# Arduino_DUE.net
KiCad netlist of a schematic drawn in Altium Designer
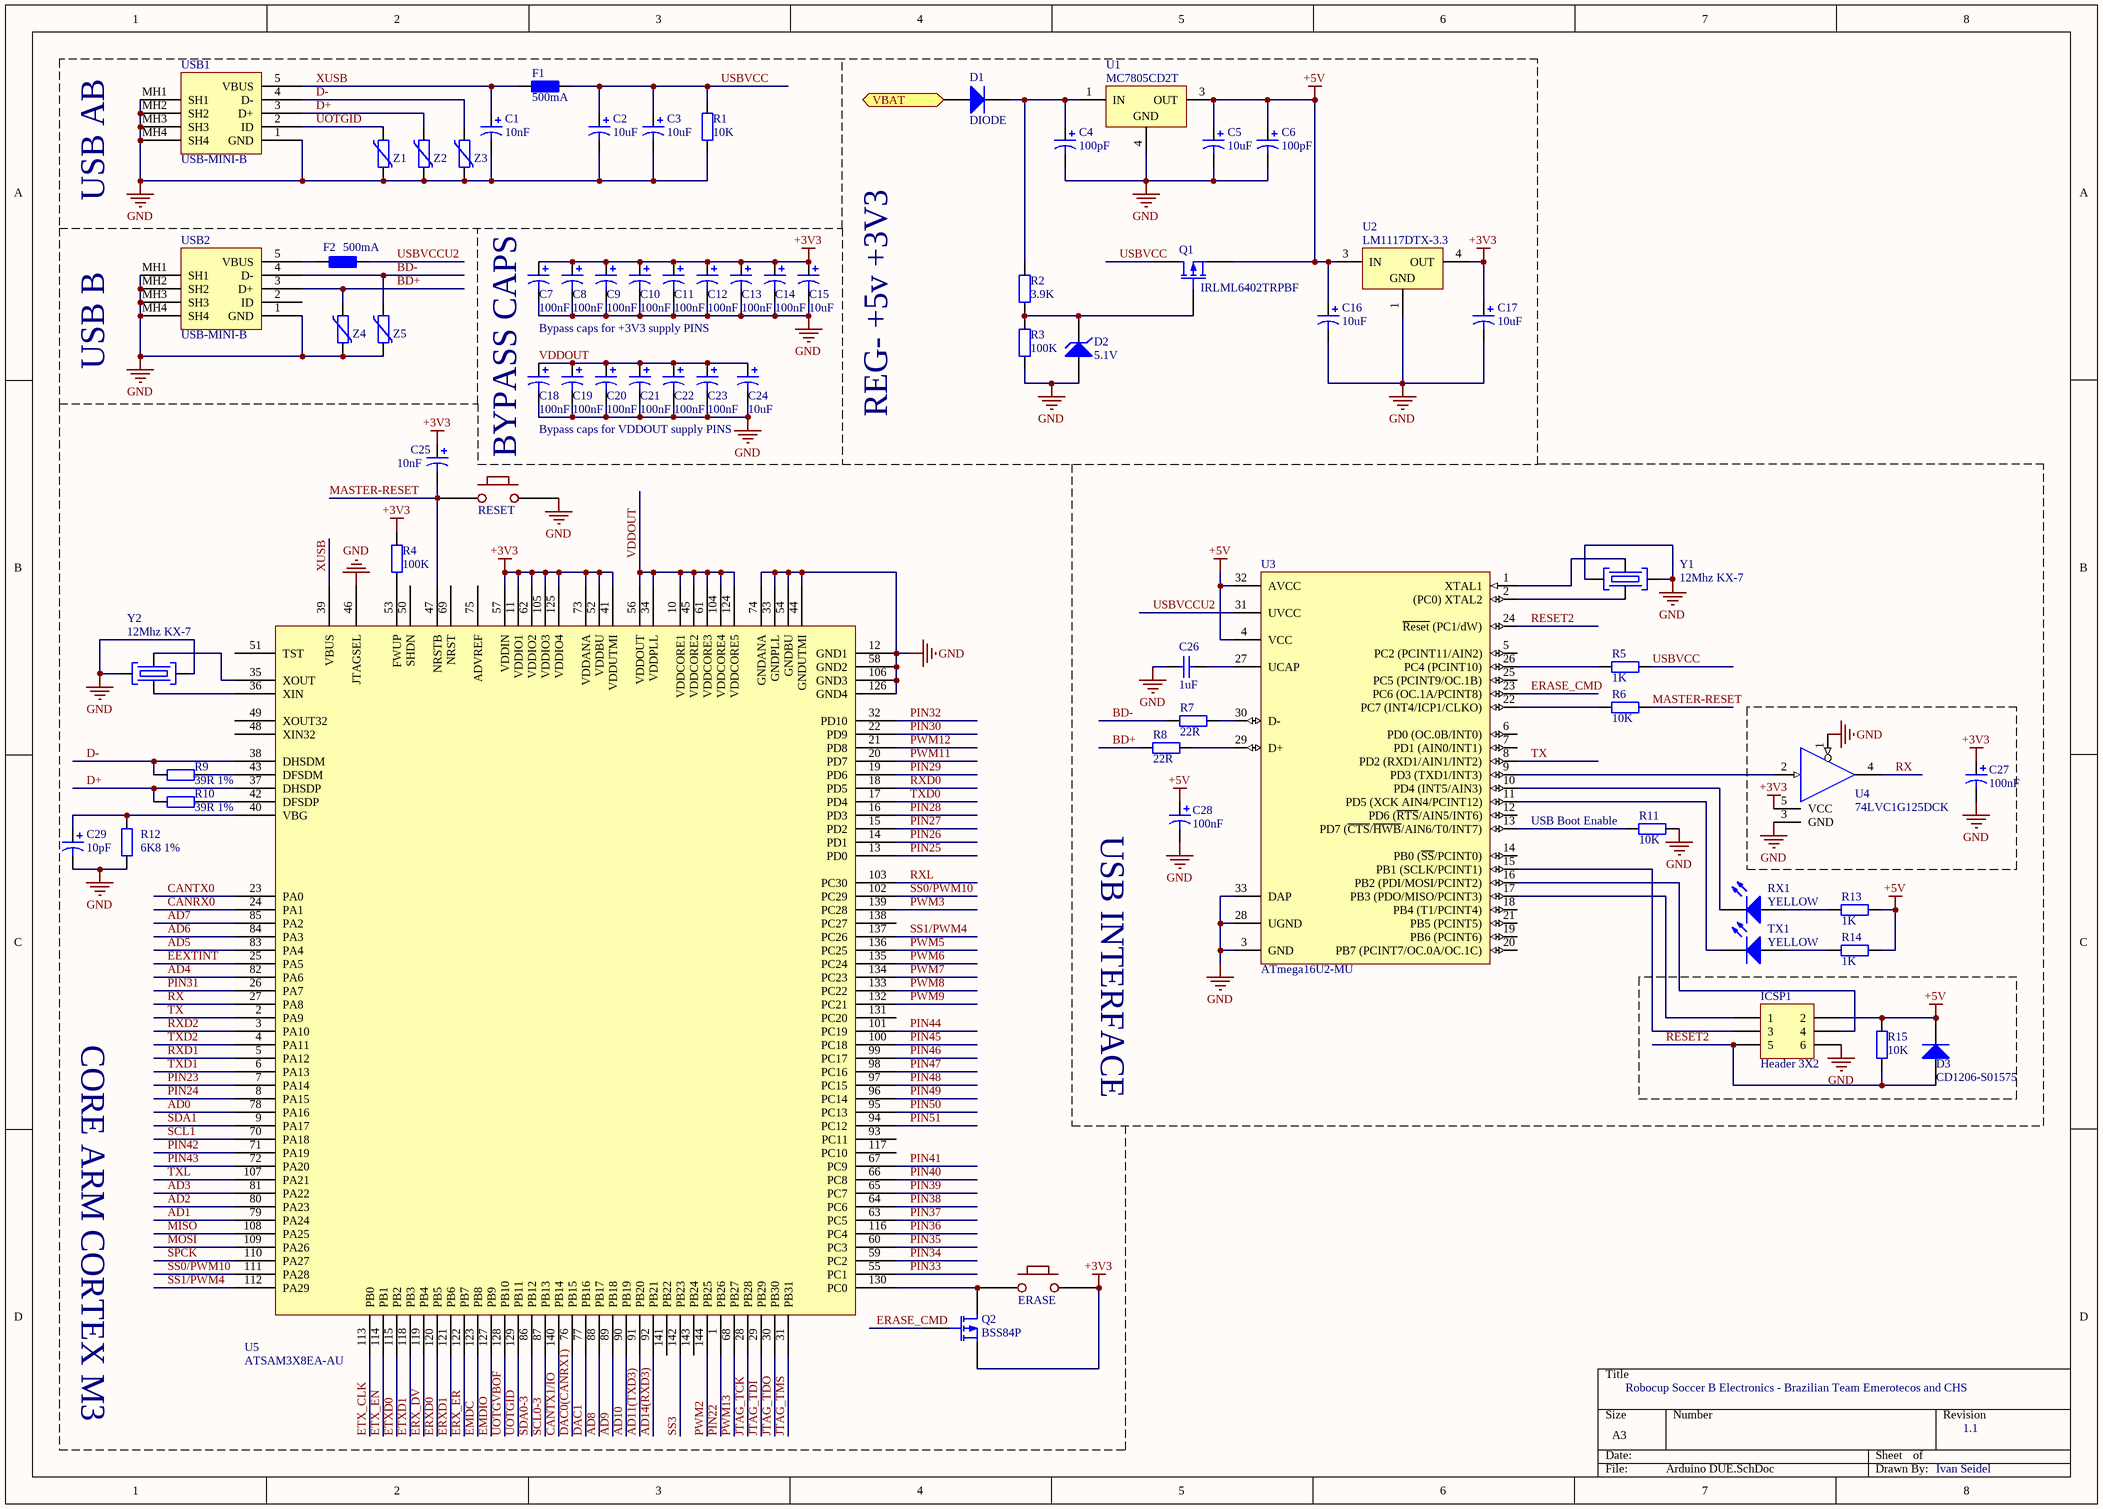
[diagram p0: Arduino DUE.SchDoc]

(export (version "E")
  (design (tool "Eeschema 10.0.6"))
  (components
    (comp (ref "C1")
      (value "10nF")
      (footprint "C0805")
      (description "Polarized Capacitor (Surface Mount)")
      (fields (field (name "PUBLISHER") "Altium Limited"))
      (libsource (lib "Miscellaneous Devices") (part "Cap Pol3"))
    )
    (comp (ref "C2")
      (value "10uF")
      (footprint "3528")
      (description "Polarized Capacitor (Surface Mount)")
      (fields (field (name "PUBLISHER") "Altium Limited"))
      (libsource (lib "Miscellaneous Devices") (part "Cap Pol3"))
    )
    (comp (ref "C3")
      (value "10uF")
      (footprint "3528")
      (description "Polarized Capacitor (Surface Mount)")
      (fields (field (name "PUBLISHER") "Altium Limited"))
      (libsource (lib "Miscellaneous Devices") (part "Cap Pol3"))
    )
    (comp (ref "C4")
      (value "100pF")
      (footprint "C0805")
      (description "Polarized Capacitor (Surface Mount)")
      (fields (field (name "PUBLISHER") "Altium Limited"))
      (libsource (lib "Miscellaneous Devices") (part "Cap Pol3"))
    )
    (comp (ref "C5")
      (value "10uF")
      (footprint "3528")
      (description "Polarized Capacitor (Surface Mount)")
      (fields (field (name "PUBLISHER") "Altium Limited"))
      (libsource (lib "Miscellaneous Devices") (part "Cap Pol3"))
    )
    (comp (ref "C6")
      (value "100pF")
      (footprint "C0805")
      (description "Polarized Capacitor (Surface Mount)")
      (fields (field (name "PUBLISHER") "Altium Limited"))
      (libsource (lib "Miscellaneous Devices") (part "Cap Pol3"))
    )
    (comp (ref "C7")
      (value "100nF")
      (footprint "C0805")
      (description "Polarized Capacitor (Surface Mount)")
      (fields (field (name "PUBLISHER") "Altium Limited"))
      (libsource (lib "Miscellaneous Devices") (part "Cap Pol3"))
    )
    (comp (ref "C8")
      (value "100nF")
      (footprint "C0805")
      (description "Polarized Capacitor (Surface Mount)")
      (fields (field (name "PUBLISHER") "Altium Limited"))
      (libsource (lib "Miscellaneous Devices") (part "Cap Pol3"))
    )
    (comp (ref "C9")
      (value "100nF")
      (footprint "C0805")
      (description "Polarized Capacitor (Surface Mount)")
      (fields (field (name "PUBLISHER") "Altium Limited"))
      (libsource (lib "Miscellaneous Devices") (part "Cap Pol3"))
    )
    (comp (ref "C10")
      (value "100nF")
      (footprint "C0805")
      (description "Polarized Capacitor (Surface Mount)")
      (fields (field (name "PUBLISHER") "Altium Limited"))
      (libsource (lib "Miscellaneous Devices") (part "Cap Pol3"))
    )
    (comp (ref "C11")
      (value "100nF")
      (footprint "C0805")
      (description "Polarized Capacitor (Surface Mount)")
      (fields (field (name "PUBLISHER") "Altium Limited"))
      (libsource (lib "Miscellaneous Devices") (part "Cap Pol3"))
    )
    (comp (ref "C12")
      (value "100nF")
      (footprint "C0805")
      (description "Polarized Capacitor (Surface Mount)")
      (fields (field (name "PUBLISHER") "Altium Limited"))
      (libsource (lib "Miscellaneous Devices") (part "Cap Pol3"))
    )
    (comp (ref "C13")
      (value "100nF")
      (footprint "C0805")
      (description "Polarized Capacitor (Surface Mount)")
      (fields (field (name "PUBLISHER") "Altium Limited"))
      (libsource (lib "Miscellaneous Devices") (part "Cap Pol3"))
    )
    (comp (ref "C14")
      (value "100nF")
      (footprint "C0805")
      (description "Polarized Capacitor (Surface Mount)")
      (fields (field (name "PUBLISHER") "Altium Limited"))
      (libsource (lib "Miscellaneous Devices") (part "Cap Pol3"))
    )
    (comp (ref "C15")
      (value "10uF")
      (footprint "3528")
      (description "Polarized Capacitor (Surface Mount)")
      (fields (field (name "PUBLISHER") "Altium Limited"))
      (libsource (lib "Miscellaneous Devices") (part "Cap Pol3"))
    )
    (comp (ref "C16")
      (value "10uF")
      (footprint "3528")
      (description "Polarized Capacitor (Surface Mount)")
      (fields (field (name "PUBLISHER") "Altium Limited"))
      (libsource (lib "Miscellaneous Devices") (part "Cap Pol3"))
    )
    (comp (ref "C17")
      (value "10uF")
      (footprint "3528")
      (description "Polarized Capacitor (Surface Mount)")
      (fields (field (name "PUBLISHER") "Altium Limited"))
      (libsource (lib "Miscellaneous Devices") (part "Cap Pol3"))
    )
    (comp (ref "C18")
      (value "100nF")
      (footprint "C0805")
      (description "Polarized Capacitor (Surface Mount)")
      (fields (field (name "PUBLISHER") "Altium Limited"))
      (libsource (lib "Miscellaneous Devices") (part "Cap Pol3"))
    )
    (comp (ref "C19")
      (value "100nF")
      (footprint "C0805")
      (description "Polarized Capacitor (Surface Mount)")
      (fields (field (name "PUBLISHER") "Altium Limited"))
      (libsource (lib "Miscellaneous Devices") (part "Cap Pol3"))
    )
    (comp (ref "C20")
      (value "100nF")
      (footprint "C0805")
      (description "Polarized Capacitor (Surface Mount)")
      (fields (field (name "PUBLISHER") "Altium Limited"))
      (libsource (lib "Miscellaneous Devices") (part "Cap Pol3"))
    )
    (comp (ref "C21")
      (value "100nF")
      (footprint "C0805")
      (description "Polarized Capacitor (Surface Mount)")
      (fields (field (name "PUBLISHER") "Altium Limited"))
      (libsource (lib "Miscellaneous Devices") (part "Cap Pol3"))
    )
    (comp (ref "C22")
      (value "100nF")
      (footprint "C0805")
      (description "Polarized Capacitor (Surface Mount)")
      (fields (field (name "PUBLISHER") "Altium Limited"))
      (libsource (lib "Miscellaneous Devices") (part "Cap Pol3"))
    )
    (comp (ref "C23")
      (value "100nF")
      (footprint "C0805")
      (description "Polarized Capacitor (Surface Mount)")
      (fields (field (name "PUBLISHER") "Altium Limited"))
      (libsource (lib "Miscellaneous Devices") (part "Cap Pol3"))
    )
    (comp (ref "C24")
      (value "10uF")
      (footprint "3528")
      (description "Polarized Capacitor (Surface Mount)")
      (fields (field (name "PUBLISHER") "Altium Limited"))
      (libsource (lib "Miscellaneous Devices") (part "Cap Pol3"))
    )
    (comp (ref "C25")
      (value "10nF")
      (footprint "C0805")
      (description "Polarized Capacitor (Surface Mount)")
      (fields (field (name "PUBLISHER") "Altium Limited"))
      (libsource (lib "Miscellaneous Devices") (part "Cap Pol3"))
    )
    (comp (ref "C26")
      (value "1uF")
      (footprint "0402")
      (description "Capacitor (Semiconductor SIM Model)")
      (fields (field (name "PUBLISHER") "Altium Limited"))
      (libsource (lib "Miscellaneous Devices") (part "Cap Semi"))
    )
    (comp (ref "C27")
      (value "100nF")
      (footprint "C0805")
      (description "Polarized Capacitor (Surface Mount)")
      (fields (field (name "PUBLISHER") "Altium Limited"))
      (libsource (lib "Miscellaneous Devices") (part "Cap Pol3"))
    )
    (comp (ref "C28")
      (value "100nF")
      (footprint "C0805")
      (description "Polarized Capacitor (Surface Mount)")
      (fields (field (name "PUBLISHER") "Altium Limited"))
      (libsource (lib "Miscellaneous Devices") (part "Cap Pol3"))
    )
    (comp (ref "C29")
      (value "10pF")
      (footprint "C0805")
      (description "Polarized Capacitor (Surface Mount)")
      (fields (field (name "PUBLISHER") "Altium Limited"))
      (libsource (lib "Miscellaneous Devices") (part "Cap Pol3"))
    )
    (comp (ref "D1") (value "DIODE") (footprint "DIODESMA") (libsource (lib "CustomLibrary") (part "DIODE")))
    (comp (ref "D2")
      (value "5.1V")
      (footprint "DIODE-SOD-123")
      (description "ZENER DIODE")
      (libsource (lib "CustomLibrary") (part "ZENER"))
    )
    (comp (ref "D3")
      (value "CD1206-S01575")
      (footprint "DIODE1206")
      (libsource (lib "CustomLibrary") (part "DIODE"))
    )
    (comp (ref "ERASE")
      (value "PUSH BUTTON")
      (footprint "PUSH-BUTTON 5,2X1,6MM")
      (libsource (lib "CustomLibrary") (part "PUSH BUTTON"))
    )
    (comp (ref "F1")
      (value "500mA")
      (footprint "MF-MSMF")
      (description "MF-MSMF Series - PTC Resettable Fuses")
      (libsource (lib "CustomLibrary") (part "MF-MSMF"))
    )
    (comp (ref "F2")
      (value "500mA")
      (footprint "MF-MSMF")
      (description "MF-MSMF Series - PTC Resettable Fuses")
      (libsource (lib "CustomLibrary") (part "MF-MSMF"))
    )
    (comp (ref "ICSP1")
      (value "Header 3X2")
      (footprint "HDR2X3")
      (description "Header, 3-Pin, Dual row")
      (fields (field (name "PUBLISHER") "Altium Limited"))
      (libsource (lib "Miscellaneous Connectors") (part "Header 3X2"))
    )
    (comp (ref "Q1")
      (value "IRLML6402TRPBF")
      (footprint "SOT-23")
      (description "P-Channel MOSFET")
      (fields (field (name "PUBLISHER") "Altium Limited"))
      (libsource (lib "CustomLibrary") (part "MOSFET-P"))
    )
    (comp (ref "Q2")
      (value "BSS84P")
      (footprint "SOT-23")
      (description "P-Channel MOSFET")
      (fields (field (name "PUBLISHER") "Altium Limited"))
      (libsource (lib "CustomLibrary") (part "MOSFET-P"))
    )
    (comp (ref "R1") (value "10K") (footprint "RES1206") (libsource (lib "") (part "RES_1")))
    (comp (ref "R2") (value "3.9K") (footprint "RES1206") (libsource (lib "") (part "RES_1")))
    (comp (ref "R3") (value "100K") (footprint "RES1206") (libsource (lib "") (part "RES_1")))
    (comp (ref "R4") (value "100K") (footprint "RES1206") (libsource (lib "") (part "RES_1")))
    (comp (ref "R5") (value "1K") (footprint "RES1206") (libsource (lib "CustomLibrary") (part "RES")))
    (comp (ref "R6") (value "10K") (footprint "RES1206") (libsource (lib "CustomLibrary") (part "RES")))
    (comp (ref "R7") (value "22R") (footprint "RES1206") (libsource (lib "CustomLibrary") (part "RES")))
    (comp (ref "R8") (value "22R") (footprint "RES1206") (libsource (lib "CustomLibrary") (part "RES")))
    (comp (ref "R9") (value "39R 1%") (footprint "RES1206") (libsource (lib "") (part "RES_2")))
    (comp (ref "R10") (value "39R 1%") (footprint "RES1206") (libsource (lib "") (part "RES_2")))
    (comp (ref "R11") (value "10K") (footprint "RES1206") (libsource (lib "CustomLibrary") (part "RES")))
    (comp (ref "R12") (value "6K8 1%") (footprint "RES1206") (libsource (lib "") (part "RES_1")))
    (comp (ref "R13") (value "1K") (footprint "RES1206") (libsource (lib "CustomLibrary") (part "RES")))
    (comp (ref "R14") (value "1K") (footprint "RES1206") (libsource (lib "CustomLibrary") (part "RES")))
    (comp (ref "R15") (value "10K") (footprint "RES1206") (libsource (lib "") (part "RES_1")))
    (comp (ref "RESET")
      (value "RESET")
      (footprint "PUSH-BUTTON 5,2X1,6MM")
      (libsource (lib "CustomLibrary") (part "PUSH BUTTON"))
    )
    (comp (ref "RX1") (value "YELLOW") (footprint "LED0805") (libsource (lib "CustomLibrary") (part "LED")))
    (comp (ref "TX1") (value "YELLOW") (footprint "LED0805") (libsource (lib "CustomLibrary") (part "LED")))
    (comp (ref "U1")
      (value "MC7805CD2T")
      (footprint "936-03")
      (description "Three-Terminal Positive Voltage Regulator")
      (fields (field (name "PUBLISHER") "Altium Limited"))
      (libsource (lib "ON Semi Power Mgt Voltage Regulator") (part "MC7805CD2T"))
    )
    (comp (ref "U2")
      (value "LM1117DTX-3.3")
      (footprint "TD03B_N")
      (description "800mA Low-Dropout Linear Regulator, 3-pin TO-252")
      (fields
        (field (name "MANUFACTURER") "National Semiconductor")
        (field (name "PUBLISHER") "Altium Limited")
      )
      (libsource (lib "NSC LDO") (part "LM1117DTX-3.3"))
    )
    (comp (ref "U3")
      (value "ATmega16U2-MU")
      (footprint "32PG_N")
      (fields (field (name "PUBLISHER") "Altium Limited"))
      (libsource (lib "Atmel Microcontroller 8-Bit megaAVR") (part "ATmega16U2-MU"))
    )
    (comp (ref "U4")
      (value "74LVC1G125DCK")
      (footprint "SC70-5")
      (libsource (lib "CustomLibrary") (part "74LVC1G125DCK"))
    )
    (comp (ref "U5")
      (value "ATSAM3X8EA-AU")
      (footprint "LQFP144_M")
      (description "ATSAM3X8EA-AU ARM CORTEX M3 Microcontroller")
      (libsource (lib "CustomLibrary") (part "ATSAM3X8E"))
    )
    (comp (ref "USB1")
      (value "USB-MINI-B")
      (footprint "USB-MINI-B")
      (description "USB Mini type B Horizontal SMD")
      (libsource (lib "CustomLibrary") (part "USB-MINI-B"))
    )
    (comp (ref "USB2")
      (value "USB-MINI-B")
      (footprint "USB-MINI-B")
      (description "USB Mini type B Horizontal SMD")
      (libsource (lib "CustomLibrary") (part "USB-MINI-B"))
    )
    (comp (ref "Y1")
      (value "12Mhz KX-7")
      (footprint "OSC-4-PIN")
      (description "KX-7 12MHz Oscilator 20pF")
      (libsource (lib "CustomLibrary") (part "OSC-4-PIN"))
    )
    (comp (ref "Y2")
      (value "12Mhz KX-7")
      (footprint "OSC-4-PIN")
      (description "KX-7 12MHz Oscilator 20pF")
      (libsource (lib "CustomLibrary") (part "OSC-4-PIN"))
    )
    (comp (ref "Z1")
      (value "ESD")
      (footprint "ESD0603")
      (description "ESD Protection Diode")
      (libsource (lib "CustomLibrary") (part "ESD"))
    )
    (comp (ref "Z2")
      (value "ESD")
      (footprint "ESD0603")
      (description "ESD Protection Diode")
      (libsource (lib "CustomLibrary") (part "ESD"))
    )
    (comp (ref "Z3")
      (value "ESD")
      (footprint "ESD0603")
      (description "ESD Protection Diode")
      (libsource (lib "CustomLibrary") (part "ESD"))
    )
    (comp (ref "Z4")
      (value "ESD")
      (footprint "ESD0603")
      (description "ESD Protection Diode")
      (libsource (lib "CustomLibrary") (part "ESD"))
    )
    (comp (ref "Z5")
      (value "ESD")
      (footprint "ESD0603")
      (description "ESD Protection Diode")
      (libsource (lib "CustomLibrary") (part "ESD"))
    )
  )
  (nets
    (net (code "1") (name "+3V3") (class "Default")
      (node (ref "C10") (pin "1") (pinfunction "1_1") (pintype "passive"))
      (node (ref "C11") (pin "1") (pinfunction "1_1") (pintype "passive"))
      (node (ref "C12") (pin "1") (pinfunction "1_1") (pintype "passive"))
      (node (ref "C13") (pin "1") (pinfunction "1_1") (pintype "passive"))
      (node (ref "C14") (pin "1") (pinfunction "1_1") (pintype "passive"))
      (node (ref "C15") (pin "1") (pinfunction "1_1") (pintype "passive"))
      (node (ref "C17") (pin "1") (pinfunction "1_1") (pintype "passive"))
      (node (ref "C25") (pin "1") (pinfunction "1_1") (pintype "passive"))
      (node (ref "C27") (pin "1") (pinfunction "1_1") (pintype "passive"))
      (node (ref "C7") (pin "1") (pinfunction "1_1") (pintype "passive"))
      (node (ref "C8") (pin "1") (pinfunction "1_1") (pintype "passive"))
      (node (ref "C9") (pin "1") (pinfunction "1_1") (pintype "passive"))
      (node (ref "ERASE") (pin "2") (pinfunction "2_2") (pintype "passive"))
      (node (ref "Q2") (pin "2") (pinfunction "S_2") (pintype "passive"))
      (node (ref "R4") (pin "2") (pinfunction "2_2") (pintype "passive"))
      (node (ref "U2") (pin "4") (pinfunction "OUT_4") (pintype "power_in"))
      (node (ref "U4") (pin "5") (pinfunction "VCC_5") (pintype "power_in"))
      (node (ref "U5") (pin "105") (pinfunction "VDDIO3_105") (pintype "power_in"))
      (node (ref "U5") (pin "11") (pinfunction "VDDIO1_11") (pintype "power_in"))
      (node (ref "U5") (pin "125") (pinfunction "VDDIO4_125") (pintype "power_in"))
      (node (ref "U5") (pin "41") (pinfunction "VDDUTMI_41") (pintype "power_in"))
      (node (ref "U5") (pin "52") (pinfunction "VDDBU_52") (pintype "power_in"))
      (node (ref "U5") (pin "57") (pinfunction "VDDIN_57") (pintype "power_in"))
      (node (ref "U5") (pin "62") (pinfunction "VDDIO2_62") (pintype "power_in"))
      (node (ref "U5") (pin "73") (pinfunction "VDDANA_73") (pintype "power_in"))
    )
    (net (code "2") (name "+5V") (class "Default")
      (node (ref "C16") (pin "1") (pinfunction "1_1") (pintype "passive"))
      (node (ref "C28") (pin "1") (pinfunction "1_1") (pintype "passive"))
      (node (ref "C5") (pin "1") (pinfunction "1_1") (pintype "passive"))
      (node (ref "C6") (pin "1") (pinfunction "1_1") (pintype "passive"))
      (node (ref "D3") (pin "1") (pinfunction "K_1") (pintype "passive"))
      (node (ref "ICSP1") (pin "2") (pinfunction "2_2") (pintype "passive"))
      (node (ref "Q1") (pin "2") (pinfunction "S_2") (pintype "passive"))
      (node (ref "R13") (pin "2") (pinfunction "2_2") (pintype "passive"))
      (node (ref "R14") (pin "2") (pinfunction "2_2") (pintype "passive"))
      (node (ref "R15") (pin "2") (pinfunction "2_2") (pintype "passive"))
      (node (ref "U1") (pin "3") (pinfunction "OUT_3") (pintype "power_in"))
      (node (ref "U2") (pin "3") (pinfunction "IN_3") (pintype "power_in"))
      (node (ref "U3") (pin "32") (pinfunction "AVCC_32") (pintype "power_in"))
      (node (ref "U3") (pin "4") (pinfunction "VCC_4") (pintype "power_in"))
    )
    (net (code "3") (name "/AD0") (class "Default")
      (node (ref "U5") (pin "78") (pinfunction "PA16_78") (pintype "passive"))
    )
    (net (code "4") (name "/AD1") (class "Default")
      (node (ref "U5") (pin "79") (pinfunction "PA24_79") (pintype "passive"))
    )
    (net (code "5") (name "/AD2") (class "Default")
      (node (ref "U5") (pin "80") (pinfunction "PA23_80") (pintype "passive"))
    )
    (net (code "6") (name "/AD3") (class "Default")
      (node (ref "U5") (pin "81") (pinfunction "PA22_81") (pintype "passive"))
    )
    (net (code "7") (name "/AD4") (class "Default")
      (node (ref "U5") (pin "82") (pinfunction "PA6_82") (pintype "passive"))
    )
    (net (code "8") (name "/AD5") (class "Default")
      (node (ref "U5") (pin "83") (pinfunction "PA4_83") (pintype "passive"))
    )
    (net (code "9") (name "/AD6") (class "Default")
      (node (ref "U5") (pin "84") (pinfunction "PA3_84") (pintype "passive"))
    )
    (net (code "10") (name "/AD7") (class "Default")
      (node (ref "U5") (pin "85") (pinfunction "PA2_85") (pintype "passive"))
    )
    (net (code "11") (name "/AD8") (class "Default")
      (node (ref "U5") (pin "88") (pinfunction "PB17_88") (pintype "passive"))
    )
    (net (code "12") (name "/AD9") (class "Default")
      (node (ref "U5") (pin "89") (pinfunction "PB18_89") (pintype "passive"))
    )
    (net (code "13") (name "/AD10") (class "Default")
      (node (ref "U5") (pin "90") (pinfunction "PB19_90") (pintype "passive"))
    )
    (net (code "14") (name "/AD11(TXD3)") (class "Default")
      (node (ref "U5") (pin "91") (pinfunction "PB20_91") (pintype "passive"))
    )
    (net (code "15") (name "/AD14(RXD3)") (class "Default")
      (node (ref "U5") (pin "92") (pinfunction "PB21_92") (pintype "passive"))
    )
    (net (code "16") (name "/BD+") (class "Default")
      (node (ref "R8") (pin "1") (pinfunction "1_1") (pintype "passive"))
      (node (ref "USB2") (pin "3") (pinfunction "D+_3") (pintype "passive"))
      (node (ref "Z4") (pin "2") (pinfunction "2_2") (pintype "passive"))
    )
    (net (code "17") (name "/BD-") (class "Default")
      (node (ref "R7") (pin "1") (pinfunction "1_1") (pintype "passive"))
      (node (ref "USB2") (pin "4") (pinfunction "D-_4") (pintype "passive"))
      (node (ref "Z5") (pin "2") (pinfunction "2_2") (pintype "passive"))
    )
    (net (code "18") (name "/CANRX0") (class "Default")
      (node (ref "U5") (pin "24") (pinfunction "PA1_24") (pintype "passive"))
    )
    (net (code "19") (name "/CANTX0") (class "Default")
      (node (ref "U5") (pin "23") (pinfunction "PA0_23") (pintype "passive"))
    )
    (net (code "20") (name "/CANTX1{slash}IO") (class "Default")
      (node (ref "U5") (pin "140") (pinfunction "PB14_140") (pintype "passive"))
    )
    (net (code "21") (name "/D+") (class "Default")
      (node (ref "R10") (pin "2") (pinfunction "2_2") (pintype "passive"))
      (node (ref "U5") (pin "37") (pinfunction "DHSDP_37") (pintype "passive"))
      (node (ref "USB1") (pin "3") (pinfunction "D+_3") (pintype "passive"))
      (node (ref "Z2") (pin "2") (pinfunction "2_2") (pintype "passive"))
    )
    (net (code "22") (name "/D-") (class "Default")
      (node (ref "R9") (pin "2") (pinfunction "2_2") (pintype "passive"))
      (node (ref "U5") (pin "38") (pinfunction "DHSDM_38") (pintype "passive"))
      (node (ref "USB1") (pin "4") (pinfunction "D-_4") (pintype "passive"))
      (node (ref "Z3") (pin "2") (pinfunction "2_2") (pintype "passive"))
    )
    (net (code "23") (name "/DAC0(CANRX1)") (class "Default")
      (node (ref "U5") (pin "76") (pinfunction "PB15_76") (pintype "passive"))
    )
    (net (code "24") (name "/DAC1") (class "Default")
      (node (ref "U5") (pin "77") (pinfunction "PB16_77") (pintype "passive"))
    )
    (net (code "25") (name "/EEXTINT") (class "Default")
      (node (ref "U5") (pin "25") (pinfunction "PA5_25") (pintype "passive"))
    )
    (net (code "26") (name "/EMDC") (class "Default")
      (node (ref "U5") (pin "123") (pinfunction "PB8_123") (pintype "passive"))
    )
    (net (code "27") (name "/EMDIO") (class "Default")
      (node (ref "U5") (pin "127") (pinfunction "PB9_127") (pintype "passive"))
    )
    (net (code "28") (name "/ERASE_CMD") (class "Default")
      (node (ref "Q2") (pin "1") (pinfunction "G_1") (pintype "passive"))
      (node (ref "U3") (pin "23") (pinfunction "PC6_(OC.1A/PCINT8)_23") (pintype "bidirectional"))
    )
    (net (code "29") (name "/ERXD0") (class "Default")
      (node (ref "U5") (pin "120") (pinfunction "PB5_120") (pintype "passive"))
    )
    (net (code "30") (name "/ERXD1") (class "Default")
      (node (ref "U5") (pin "121") (pinfunction "PB6_121") (pintype "passive"))
    )
    (net (code "31") (name "/ERX_DV") (class "Default")
      (node (ref "U5") (pin "119") (pinfunction "PB4_119") (pintype "passive"))
    )
    (net (code "32") (name "/ERX_ER") (class "Default")
      (node (ref "U5") (pin "122") (pinfunction "PB7_122") (pintype "passive"))
    )
    (net (code "33") (name "/ETXD0") (class "Default")
      (node (ref "U5") (pin "115") (pinfunction "PB2_115") (pintype "passive"))
    )
    (net (code "34") (name "/ETXD1") (class "Default")
      (node (ref "U5") (pin "118") (pinfunction "PB3_118") (pintype "passive"))
    )
    (net (code "35") (name "/ETX_CLK") (class "Default")
      (node (ref "U5") (pin "113") (pinfunction "PB0_113") (pintype "passive"))
    )
    (net (code "36") (name "/ETX_EN") (class "Default")
      (node (ref "U5") (pin "114") (pinfunction "PB1_114") (pintype "passive"))
    )
    (net (code "37") (name "/JTAG_TCK") (class "Default")
      (node (ref "U5") (pin "28") (pinfunction "PB28_28") (pintype "passive"))
    )
    (net (code "38") (name "/JTAG_TDI") (class "Default")
      (node (ref "U5") (pin "29") (pinfunction "PB29_29") (pintype "passive"))
    )
    (net (code "39") (name "/JTAG_TDO") (class "Default")
      (node (ref "U5") (pin "30") (pinfunction "PB30_30") (pintype "passive"))
    )
    (net (code "40") (name "/JTAG_TMS") (class "Default")
      (node (ref "U5") (pin "31") (pinfunction "PB31_31") (pintype "passive"))
    )
    (net (code "41") (name "/MASTER-RESET") (class "Default")
      (node (ref "C25") (pin "2") (pinfunction "2_2") (pintype "passive"))
      (node (ref "R6") (pin "2") (pinfunction "2_2") (pintype "passive"))
      (node (ref "RESET") (pin "1") (pinfunction "1_1") (pintype "passive"))
      (node (ref "U5") (pin "47") (pinfunction "NRSTB_47") (pintype "passive"))
    )
    (net (code "42") (name "/MISO") (class "Default")
      (node (ref "U5") (pin "108") (pinfunction "PA25_108") (pintype "passive"))
    )
    (net (code "43") (name "/MOSI") (class "Default")
      (node (ref "U5") (pin "109") (pinfunction "PA26_109") (pintype "passive"))
    )
    (net (code "44") (name "/PIN22") (class "Default")
      (node (ref "U5") (pin "1") (pinfunction "PB26_1") (pintype "passive"))
    )
    (net (code "45") (name "/PIN23") (class "Default")
      (node (ref "U5") (pin "7") (pinfunction "PA14_7") (pintype "passive"))
    )
    (net (code "46") (name "/PIN24") (class "Default")
      (node (ref "U5") (pin "8") (pinfunction "PA15_8") (pintype "passive"))
    )
    (net (code "47") (name "/PIN25") (class "Default")
      (node (ref "U5") (pin "13") (pinfunction "PD0_13") (pintype "passive"))
    )
    (net (code "48") (name "/PIN26") (class "Default")
      (node (ref "U5") (pin "14") (pinfunction "PD1_14") (pintype "passive"))
    )
    (net (code "49") (name "/PIN27") (class "Default")
      (node (ref "U5") (pin "15") (pinfunction "PD2_15") (pintype "passive"))
    )
    (net (code "50") (name "/PIN28") (class "Default")
      (node (ref "U5") (pin "16") (pinfunction "PD3_16") (pintype "passive"))
    )
    (net (code "51") (name "/PIN29") (class "Default")
      (node (ref "U5") (pin "19") (pinfunction "PD6_19") (pintype "passive"))
    )
    (net (code "52") (name "/PIN30") (class "Default")
      (node (ref "U5") (pin "22") (pinfunction "PD9_22") (pintype "passive"))
    )
    (net (code "53") (name "/PIN31") (class "Default")
      (node (ref "U5") (pin "26") (pinfunction "PA7_26") (pintype "passive"))
    )
    (net (code "54") (name "/PIN32") (class "Default")
      (node (ref "U5") (pin "32") (pinfunction "PD10_32") (pintype "passive"))
    )
    (net (code "55") (name "/PIN33") (class "Default")
      (node (ref "U5") (pin "55") (pinfunction "PC1_55") (pintype "passive"))
    )
    (net (code "56") (name "/PIN34") (class "Default")
      (node (ref "U5") (pin "59") (pinfunction "PC2_59") (pintype "passive"))
    )
    (net (code "57") (name "/PIN35") (class "Default")
      (node (ref "U5") (pin "60") (pinfunction "PC3_60") (pintype "passive"))
    )
    (net (code "58") (name "/PIN36") (class "Default")
      (node (ref "U5") (pin "116") (pinfunction "PC4_116") (pintype "passive"))
    )
    (net (code "59") (name "/PIN37") (class "Default")
      (node (ref "U5") (pin "63") (pinfunction "PC5_63") (pintype "passive"))
    )
    (net (code "60") (name "/PIN38") (class "Default")
      (node (ref "U5") (pin "64") (pinfunction "PC6_64") (pintype "passive"))
    )
    (net (code "61") (name "/PIN39") (class "Default")
      (node (ref "U5") (pin "65") (pinfunction "PC7_65") (pintype "passive"))
    )
    (net (code "62") (name "/PIN40") (class "Default")
      (node (ref "U5") (pin "66") (pinfunction "PC8_66") (pintype "passive"))
    )
    (net (code "63") (name "/PIN41") (class "Default")
      (node (ref "U5") (pin "67") (pinfunction "PC9_67") (pintype "passive"))
    )
    (net (code "64") (name "/PIN42") (class "Default")
      (node (ref "U5") (pin "71") (pinfunction "PA19_71") (pintype "passive"))
    )
    (net (code "65") (name "/PIN43") (class "Default")
      (node (ref "U5") (pin "72") (pinfunction "PA20_72") (pintype "passive"))
    )
    (net (code "66") (name "/PIN44") (class "Default")
      (node (ref "U5") (pin "101") (pinfunction "PC19_101") (pintype "passive"))
    )
    (net (code "67") (name "/PIN45") (class "Default")
      (node (ref "U5") (pin "100") (pinfunction "PC18_100") (pintype "passive"))
    )
    (net (code "68") (name "/PIN46") (class "Default")
      (node (ref "U5") (pin "99") (pinfunction "PC17_99") (pintype "passive"))
    )
    (net (code "69") (name "/PIN47") (class "Default")
      (node (ref "U5") (pin "98") (pinfunction "PC16_98") (pintype "passive"))
    )
    (net (code "70") (name "/PIN48") (class "Default")
      (node (ref "U5") (pin "97") (pinfunction "PC15_97") (pintype "passive"))
    )
    (net (code "71") (name "/PIN49") (class "Default")
      (node (ref "U5") (pin "96") (pinfunction "PC14_96") (pintype "passive"))
    )
    (net (code "72") (name "/PIN50") (class "Default")
      (node (ref "U5") (pin "95") (pinfunction "PC13_95") (pintype "passive"))
    )
    (net (code "73") (name "/PIN51") (class "Default")
      (node (ref "U5") (pin "94") (pinfunction "PC12_94") (pintype "passive"))
    )
    (net (code "74") (name "/PWM2") (class "Default")
      (node (ref "U5") (pin "144") (pinfunction "PB25_144") (pintype "passive"))
    )
    (net (code "75") (name "/PWM3") (class "Default")
      (node (ref "U5") (pin "139") (pinfunction "PC28_139") (pintype "passive"))
    )
    (net (code "76") (name "/PWM5") (class "Default")
      (node (ref "U5") (pin "136") (pinfunction "PC25_136") (pintype "passive"))
    )
    (net (code "77") (name "/PWM6") (class "Default")
      (node (ref "U5") (pin "135") (pinfunction "PC24_135") (pintype "passive"))
    )
    (net (code "78") (name "/PWM7") (class "Default")
      (node (ref "U5") (pin "134") (pinfunction "PC23_134") (pintype "passive"))
    )
    (net (code "79") (name "/PWM8") (class "Default")
      (node (ref "U5") (pin "133") (pinfunction "PC22_133") (pintype "passive"))
    )
    (net (code "80") (name "/PWM9") (class "Default")
      (node (ref "U5") (pin "132") (pinfunction "PC21_132") (pintype "passive"))
    )
    (net (code "81") (name "/PWM11") (class "Default")
      (node (ref "U5") (pin "20") (pinfunction "PD7_20") (pintype "passive"))
    )
    (net (code "82") (name "/PWM12") (class "Default")
      (node (ref "U5") (pin "21") (pinfunction "PD8_21") (pintype "passive"))
    )
    (net (code "83") (name "/PWM13") (class "Default")
      (node (ref "U5") (pin "68") (pinfunction "PB27_68") (pintype "passive"))
    )
    (net (code "84") (name "/RESET2") (class "Default")
      (node (ref "D3") (pin "2") (pinfunction "A_2") (pintype "passive"))
      (node (ref "ICSP1") (pin "5") (pinfunction "5_5") (pintype "passive"))
      (node (ref "R15") (pin "1") (pinfunction "1_1") (pintype "passive"))
      (node (ref "U3") (pin "24") (pinfunction "~{Reset}_(PC1/dW)_24") (pintype "bidirectional"))
    )
    (net (code "85") (name "/RX") (class "Default")
      (node (ref "U4") (pin "4") (pinfunction "4_4") (pintype "passive"))
      (node (ref "U5") (pin "27") (pinfunction "PA8_27") (pintype "passive"))
    )
    (net (code "86") (name "/RXD0") (class "Default")
      (node (ref "U5") (pin "18") (pinfunction "PD5_18") (pintype "passive"))
    )
    (net (code "87") (name "/RXD1") (class "Default")
      (node (ref "U5") (pin "5") (pinfunction "PA12_5") (pintype "passive"))
    )
    (net (code "88") (name "/RXD2") (class "Default")
      (node (ref "U5") (pin "3") (pinfunction "PA10_3") (pintype "passive"))
    )
    (net (code "89") (name "/RXL") (class "Default")
      (node (ref "U5") (pin "103") (pinfunction "PC30_103") (pintype "passive"))
    )
    (net (code "90") (name "/SCL0-3") (class "Default")
      (node (ref "U5") (pin "87") (pinfunction "PB13_87") (pintype "passive"))
    )
    (net (code "91") (name "/SCL1") (class "Default")
      (node (ref "U5") (pin "70") (pinfunction "PA18_70") (pintype "passive"))
    )
    (net (code "92") (name "/SDA0-3") (class "Default")
      (node (ref "U5") (pin "86") (pinfunction "PB12_86") (pintype "passive"))
    )
    (net (code "93") (name "/SDA1") (class "Default")
      (node (ref "U5") (pin "9") (pinfunction "PA17_9") (pintype "passive"))
    )
    (net (code "94") (name "/SPCK") (class "Default")
      (node (ref "U5") (pin "110") (pinfunction "PA27_110") (pintype "passive"))
    )
    (net (code "95") (name "/SS0{slash}PWM10") (class "Default")
      (node (ref "U5") (pin "102") (pinfunction "PC29_102") (pintype "passive"))
      (node (ref "U5") (pin "111") (pinfunction "PA28_111") (pintype "passive"))
    )
    (net (code "96") (name "/SS1{slash}PWM4") (class "Default")
      (node (ref "U5") (pin "112") (pinfunction "PA29_112") (pintype "passive"))
      (node (ref "U5") (pin "137") (pinfunction "PC26_137") (pintype "passive"))
    )
    (net (code "97") (name "/SS3") (class "Default")
      (node (ref "U5") (pin "142") (pinfunction "PB23_142") (pintype "passive"))
    )
    (net (code "98") (name "/TX") (class "Default")
      (node (ref "U3") (pin "8") (pinfunction "PD2_(RXD1/AIN1/INT2)_8") (pintype "bidirectional"))
      (node (ref "U5") (pin "2") (pinfunction "PA9_2") (pintype "passive"))
    )
    (net (code "99") (name "/TXD0") (class "Default")
      (node (ref "U5") (pin "17") (pinfunction "PD4_17") (pintype "passive"))
    )
    (net (code "100") (name "/TXD1") (class "Default")
      (node (ref "U5") (pin "6") (pinfunction "PA13_6") (pintype "passive"))
    )
    (net (code "101") (name "/TXD2") (class "Default")
      (node (ref "U5") (pin "4") (pinfunction "PA11_4") (pintype "passive"))
    )
    (net (code "102") (name "/TXL") (class "Default")
      (node (ref "U5") (pin "107") (pinfunction "PA21_107") (pintype "passive"))
    )
    (net (code "103") (name "/UOTGID") (class "Default")
      (node (ref "U5") (pin "129") (pinfunction "PB11_129") (pintype "passive"))
      (node (ref "USB1") (pin "2") (pinfunction "ID_2") (pintype "passive"))
      (node (ref "Z1") (pin "2") (pinfunction "2_2") (pintype "passive"))
    )
    (net (code "104") (name "/UOTGVBOF") (class "Default")
      (node (ref "U5") (pin "128") (pinfunction "PB10_128") (pintype "passive"))
    )
    (net (code "105") (name "/USBVCC") (class "Default")
      (node (ref "C2") (pin "1") (pinfunction "1_1") (pintype "passive"))
      (node (ref "C3") (pin "1") (pinfunction "1_1") (pintype "passive"))
      (node (ref "F1") (pin "2") (pinfunction "2_2") (pintype "passive"))
      (node (ref "Q1") (pin "3") (pinfunction "D_3") (pintype "passive"))
      (node (ref "R1") (pin "2") (pinfunction "2_2") (pintype "passive"))
      (node (ref "R5") (pin "2") (pinfunction "2_2") (pintype "passive"))
    )
    (net (code "106") (name "/USBVCCU2") (class "Default")
      (node (ref "F2") (pin "2") (pinfunction "2_2") (pintype "passive"))
      (node (ref "U3") (pin "31") (pinfunction "UVCC_31") (pintype "power_in"))
    )
    (net (code "107") (name "/VBAT") (class "Default")
      (node (ref "D1") (pin "2") (pinfunction "A_2") (pintype "passive"))
    )
    (net (code "108") (name "/VDDOUT") (class "Default")
      (node (ref "C18") (pin "1") (pinfunction "1_1") (pintype "passive"))
      (node (ref "C19") (pin "1") (pinfunction "1_1") (pintype "passive"))
      (node (ref "C20") (pin "1") (pinfunction "1_1") (pintype "passive"))
      (node (ref "C21") (pin "1") (pinfunction "1_1") (pintype "passive"))
      (node (ref "C22") (pin "1") (pinfunction "1_1") (pintype "passive"))
      (node (ref "C23") (pin "1") (pinfunction "1_1") (pintype "passive"))
      (node (ref "C24") (pin "1") (pinfunction "1_1") (pintype "passive"))
      (node (ref "U5") (pin "10") (pinfunction "VDDCORE1_10") (pintype "power_in"))
      (node (ref "U5") (pin "104") (pinfunction "VDDCORE4_104") (pintype "power_in"))
      (node (ref "U5") (pin "124") (pinfunction "VDDCORE5_124") (pintype "power_in"))
      (node (ref "U5") (pin "34") (pinfunction "VDDPLL_34") (pintype "power_in"))
      (node (ref "U5") (pin "45") (pinfunction "VDDCORE2_45") (pintype "power_in"))
      (node (ref "U5") (pin "56") (pinfunction "VDDOUT_56") (pintype "power_in"))
      (node (ref "U5") (pin "61") (pinfunction "VDDCORE3_61") (pintype "power_in"))
    )
    (net (code "109") (name "/XUSB") (class "Default")
      (node (ref "C1") (pin "1") (pinfunction "1_1") (pintype "passive"))
      (node (ref "F1") (pin "1") (pinfunction "1_1") (pintype "passive"))
      (node (ref "U5") (pin "39") (pinfunction "VBUS_39") (pintype "power_in"))
      (node (ref "USB1") (pin "5") (pinfunction "VBUS_5") (pintype "power_in"))
    )
    (net (code "110") (name "GND") (class "Default")
      (node (ref "C1") (pin "2") (pinfunction "2_2") (pintype "passive"))
      (node (ref "C10") (pin "2") (pinfunction "2_2") (pintype "passive"))
      (node (ref "C11") (pin "2") (pinfunction "2_2") (pintype "passive"))
      (node (ref "C12") (pin "2") (pinfunction "2_2") (pintype "passive"))
      (node (ref "C13") (pin "2") (pinfunction "2_2") (pintype "passive"))
      (node (ref "C14") (pin "2") (pinfunction "2_2") (pintype "passive"))
      (node (ref "C15") (pin "2") (pinfunction "2_2") (pintype "passive"))
      (node (ref "C16") (pin "2") (pinfunction "2_2") (pintype "passive"))
      (node (ref "C17") (pin "2") (pinfunction "2_2") (pintype "passive"))
      (node (ref "C18") (pin "2") (pinfunction "2_2") (pintype "passive"))
      (node (ref "C19") (pin "2") (pinfunction "2_2") (pintype "passive"))
      (node (ref "C2") (pin "2") (pinfunction "2_2") (pintype "passive"))
      (node (ref "C20") (pin "2") (pinfunction "2_2") (pintype "passive"))
      (node (ref "C21") (pin "2") (pinfunction "2_2") (pintype "passive"))
      (node (ref "C22") (pin "2") (pinfunction "2_2") (pintype "passive"))
      (node (ref "C23") (pin "2") (pinfunction "2_2") (pintype "passive"))
      (node (ref "C24") (pin "2") (pinfunction "2_2") (pintype "passive"))
      (node (ref "C26") (pin "1") (pinfunction "1_1") (pintype "passive"))
      (node (ref "C27") (pin "2") (pinfunction "2_2") (pintype "passive"))
      (node (ref "C28") (pin "2") (pinfunction "2_2") (pintype "passive"))
      (node (ref "C29") (pin "2") (pinfunction "2_2") (pintype "passive"))
      (node (ref "C3") (pin "2") (pinfunction "2_2") (pintype "passive"))
      (node (ref "C4") (pin "2") (pinfunction "2_2") (pintype "passive"))
      (node (ref "C5") (pin "2") (pinfunction "2_2") (pintype "passive"))
      (node (ref "C6") (pin "2") (pinfunction "2_2") (pintype "passive"))
      (node (ref "C7") (pin "2") (pinfunction "2_2") (pintype "passive"))
      (node (ref "C8") (pin "2") (pinfunction "2_2") (pintype "passive"))
      (node (ref "C9") (pin "2") (pinfunction "2_2") (pintype "passive"))
      (node (ref "D2") (pin "2") (pinfunction "A_2") (pintype "passive"))
      (node (ref "ICSP1") (pin "6") (pinfunction "6_6") (pintype "passive"))
      (node (ref "R1") (pin "1") (pinfunction "1_1") (pintype "passive"))
      (node (ref "R11") (pin "2") (pinfunction "2_2") (pintype "passive"))
      (node (ref "R12") (pin "1") (pinfunction "1_1") (pintype "passive"))
      (node (ref "R3") (pin "1") (pinfunction "1_1") (pintype "passive"))
      (node (ref "RESET") (pin "2") (pinfunction "2_2") (pintype "passive"))
      (node (ref "U1") (pin "4") (pinfunction "GND_4") (pintype "power_in"))
      (node (ref "U2") (pin "1") (pinfunction "GND_1") (pintype "power_in"))
      (node (ref "U3") (pin "28") (pinfunction "UGND_28") (pintype "power_in"))
      (node (ref "U3") (pin "3") (pinfunction "GND_3") (pintype "power_in"))
      (node (ref "U3") (pin "33") (pinfunction "DAP_33") (pintype "power_in"))
      (node (ref "U4") (pin "1") (pinfunction "1_1") (pintype "input"))
      (node (ref "U4") (pin "3") (pinfunction "GND_3") (pintype "power_in"))
      (node (ref "U5") (pin "106") (pinfunction "GND3_106") (pintype "power_in"))
      (node (ref "U5") (pin "12") (pinfunction "GND1_12") (pintype "power_in"))
      (node (ref "U5") (pin "126") (pinfunction "GND4_126") (pintype "power_in"))
      (node (ref "U5") (pin "33") (pinfunction "GNDPLL_33") (pintype "power_in"))
      (node (ref "U5") (pin "44") (pinfunction "GNDUTMI_44") (pintype "power_in"))
      (node (ref "U5") (pin "46") (pinfunction "JTAGSEL_46") (pintype "passive"))
      (node (ref "U5") (pin "54") (pinfunction "GNDBU_54") (pintype "power_in"))
      (node (ref "U5") (pin "58") (pinfunction "GND2_58") (pintype "power_in"))
      (node (ref "U5") (pin "74") (pinfunction "GNDANA_74") (pintype "power_in"))
      (node (ref "USB1") (pin "1") (pinfunction "GND_1") (pintype "power_in"))
      (node (ref "USB1") (pin "MH1") (pinfunction "SH1_MH1") (pintype "power_in"))
      (node (ref "USB1") (pin "MH2") (pinfunction "SH2_MH2") (pintype "power_in"))
      (node (ref "USB1") (pin "MH3") (pinfunction "SH3_MH3") (pintype "power_in"))
      (node (ref "USB1") (pin "MH4") (pinfunction "SH4_MH4") (pintype "power_in"))
      (node (ref "USB2") (pin "1") (pinfunction "GND_1") (pintype "power_in"))
      (node (ref "USB2") (pin "MH1") (pinfunction "SH1_MH1") (pintype "power_in"))
      (node (ref "USB2") (pin "MH2") (pinfunction "SH2_MH2") (pintype "power_in"))
      (node (ref "USB2") (pin "MH3") (pinfunction "SH3_MH3") (pintype "power_in"))
      (node (ref "USB2") (pin "MH4") (pinfunction "SH4_MH4") (pintype "power_in"))
      (node (ref "Y1") (pin "2") (pinfunction "2_2") (pintype "passive"))
      (node (ref "Y1") (pin "4") (pinfunction "4_4") (pintype "passive"))
      (node (ref "Y2") (pin "2") (pinfunction "2_2") (pintype "passive"))
      (node (ref "Y2") (pin "4") (pinfunction "4_4") (pintype "passive"))
      (node (ref "Z1") (pin "1") (pinfunction "1_1") (pintype "passive"))
      (node (ref "Z2") (pin "1") (pinfunction "1_1") (pintype "passive"))
      (node (ref "Z3") (pin "1") (pinfunction "1_1") (pintype "passive"))
      (node (ref "Z4") (pin "1") (pinfunction "1_1") (pintype "passive"))
      (node (ref "Z5") (pin "1") (pinfunction "1_1") (pintype "passive"))
    )
    (net (code "111") (name "Net-(D1-K)") (class "Default")
      (node (ref "C4") (pin "1") (pinfunction "1_1") (pintype "passive"))
      (node (ref "D1") (pin "1") (pinfunction "K_1") (pintype "passive"))
      (node (ref "R2") (pin "2") (pinfunction "2_2") (pintype "passive"))
      (node (ref "U1") (pin "1") (pinfunction "IN_1") (pintype "power_in"))
    )
    (net (code "112") (name "Net-(D2-K)") (class "Default")
      (node (ref "D2") (pin "1") (pinfunction "K_1") (pintype "passive"))
      (node (ref "Q1") (pin "1") (pinfunction "G_1") (pintype "passive"))
      (node (ref "R2") (pin "1") (pinfunction "1_1") (pintype "passive"))
      (node (ref "R3") (pin "2") (pinfunction "2_2") (pintype "passive"))
    )
    (net (code "113") (name "Net-(Q2-D)") (class "Default")
      (node (ref "ERASE") (pin "1") (pinfunction "1_1") (pintype "passive"))
      (node (ref "Q2") (pin "3") (pinfunction "D_3") (pintype "passive"))
      (node (ref "U5") (pin "130") (pinfunction "PC0_130") (pintype "passive"))
    )
    (net (code "114") (name "Net-(RX1-A)") (class "Default")
      (node (ref "R13") (pin "1") (pinfunction "1_1") (pintype "passive"))
      (node (ref "RX1") (pin "1") (pinfunction "A_1") (pintype "passive"))
    )
    (net (code "115") (name "Net-(RX1-K)") (class "Default")
      (node (ref "RX1") (pin "2") (pinfunction "K_2") (pintype "passive"))
      (node (ref "U3") (pin "10") (pinfunction "PD4_(INT5/AIN3)_10") (pintype "bidirectional"))
    )
    (net (code "116") (name "Net-(TX1-A)") (class "Default")
      (node (ref "R14") (pin "1") (pinfunction "1_1") (pintype "passive"))
      (node (ref "TX1") (pin "1") (pinfunction "A_1") (pintype "passive"))
    )
    (net (code "117") (name "Net-(TX1-K)") (class "Default")
      (node (ref "TX1") (pin "2") (pinfunction "K_2") (pintype "passive"))
      (node (ref "U3") (pin "11") (pinfunction "PD5_(XCK_AIN4/PCINT12)_11") (pintype "bidirectional"))
    )
    (net (code "118") (name "Net-(U3-(PC0)_XTAL2)") (class "Default")
      (node (ref "U3") (pin "2") (pinfunction "(PC0)_XTAL2_2") (pintype "bidirectional"))
      (node (ref "Y1") (pin "3") (pinfunction "3_3") (pintype "passive"))
    )
    (net (code "119") (name "Net-(U3-D+)") (class "Default")
      (node (ref "R8") (pin "2") (pinfunction "2_2") (pintype "passive"))
      (node (ref "U3") (pin "29") (pinfunction "D+_29") (pintype "bidirectional"))
    )
    (net (code "120") (name "Net-(U3-D-)") (class "Default")
      (node (ref "R7") (pin "2") (pinfunction "2_2") (pintype "passive"))
      (node (ref "U3") (pin "30") (pinfunction "D-_30") (pintype "bidirectional"))
    )
    (net (code "121") (name "Net-(U3-PB1_(SCLK{slash}PCINT1))") (class "Default")
      (node (ref "ICSP1") (pin "3") (pinfunction "3_3") (pintype "passive"))
      (node (ref "U3") (pin "15") (pinfunction "PB1_(SCLK/PCINT1)_15") (pintype "bidirectional"))
    )
    (net (code "122") (name "Net-(U3-PB2_(PDI{slash}MOSI{slash}PCINT2))") (class "Default")
      (node (ref "ICSP1") (pin "4") (pinfunction "4_4") (pintype "passive"))
      (node (ref "U3") (pin "16") (pinfunction "PB2_(PDI/MOSI/PCINT2)_16") (pintype "bidirectional"))
    )
    (net (code "123") (name "Net-(U3-PB3_(PDO{slash}MISO{slash}PCINT3))") (class "Default")
      (node (ref "ICSP1") (pin "1") (pinfunction "1_1") (pintype "passive"))
      (node (ref "U3") (pin "17") (pinfunction "PB3_(PDO/MISO/PCINT3)_17") (pintype "bidirectional"))
    )
    (net (code "124") (name "Net-(U3-PC4_(PCINT10))") (class "Default")
      (node (ref "R5") (pin "1") (pinfunction "1_1") (pintype "passive"))
      (node (ref "U3") (pin "26") (pinfunction "PC4_(PCINT10)_26") (pintype "bidirectional"))
    )
    (net (code "125") (name "Net-(U3-PC7_(INT4{slash}ICP1{slash}CLKO))") (class "Default")
      (node (ref "R6") (pin "1") (pinfunction "1_1") (pintype "passive"))
      (node (ref "U3") (pin "22") (pinfunction "PC7_(INT4/ICP1/CLKO)_22") (pintype "bidirectional"))
    )
    (net (code "126") (name "Net-(U3-PD3_(TXD1{slash}INT3))") (class "Default")
      (node (ref "U3") (pin "9") (pinfunction "PD3_(TXD1/INT3)_9") (pintype "bidirectional"))
      (node (ref "U4") (pin "2") (pinfunction "2_2") (pintype "input"))
    )
    (net (code "127") (name "Net-(U3-PD7_(~{CTS}{slash}~{HWB}{slash}AIN6{slash}T0{slash}INT7))") (class "Default")
      (node (ref "R11") (pin "1") (pinfunction "1_1") (pintype "passive"))
      (node (ref "U3") (pin "13") (pinfunction "PD7_(~{CTS}/~{HWB}/AIN6/T0/INT7)_13") (pintype "bidirectional"))
    )
    (net (code "128") (name "Net-(U3-UCAP)") (class "Default")
      (node (ref "C26") (pin "2") (pinfunction "2_2") (pintype "passive"))
      (node (ref "U3") (pin "27") (pinfunction "UCAP_27") (pintype "power_in"))
    )
    (net (code "129") (name "Net-(U3-XTAL1)") (class "Default")
      (node (ref "U3") (pin "1") (pinfunction "XTAL1_1") (pintype "input"))
      (node (ref "Y1") (pin "1") (pinfunction "1_1") (pintype "passive"))
    )
    (net (code "130") (name "Net-(U5-DFSDM)") (class "Default")
      (node (ref "R9") (pin "1") (pinfunction "1_1") (pintype "passive"))
      (node (ref "U5") (pin "43") (pinfunction "DFSDM_43") (pintype "passive"))
    )
    (net (code "131") (name "Net-(U5-DFSDP)") (class "Default")
      (node (ref "R10") (pin "1") (pinfunction "1_1") (pintype "passive"))
      (node (ref "U5") (pin "42") (pinfunction "DFSDP_42") (pintype "passive"))
    )
    (net (code "132") (name "Net-(U5-FWUP)") (class "Default")
      (node (ref "R4") (pin "1") (pinfunction "1_1") (pintype "passive"))
      (node (ref "U5") (pin "53") (pinfunction "FWUP_53") (pintype "passive"))
    )
    (net (code "133") (name "Net-(U5-VBG)") (class "Default")
      (node (ref "C29") (pin "1") (pinfunction "1_1") (pintype "passive"))
      (node (ref "R12") (pin "2") (pinfunction "2_2") (pintype "passive"))
      (node (ref "U5") (pin "40") (pinfunction "VBG_40") (pintype "passive"))
    )
    (net (code "134") (name "Net-(U5-XIN)") (class "Default")
      (node (ref "U5") (pin "36") (pinfunction "XIN_36") (pintype "passive"))
      (node (ref "Y2") (pin "3") (pinfunction "3_3") (pintype "passive"))
    )
    (net (code "135") (name "Net-(U5-XOUT)") (class "Default")
      (node (ref "U5") (pin "35") (pinfunction "XOUT_35") (pintype "passive"))
      (node (ref "Y2") (pin "1") (pinfunction "1_1") (pintype "passive"))
    )
    (net (code "136") (name "Net-(USB2-VBUS)") (class "Default")
      (node (ref "F2") (pin "1") (pinfunction "1_1") (pintype "passive"))
      (node (ref "USB2") (pin "5") (pinfunction "VBUS_5") (pintype "power_in"))
    )
    (net (code "137") (name "unconnected-(U3-PB0_(~{SS}{slash}PCINT0)-Pad14)") (class "Default")
      (node (ref "U3") (pin "14") (pinfunction "PB0_(~{SS}/PCINT0)_14") (pintype "bidirectional"))
    )
    (net (code "138") (name "unconnected-(U3-PB4_(T1{slash}PCINT4)-Pad18)") (class "Default")
      (node (ref "U3") (pin "18") (pinfunction "PB4_(T1/PCINT4)_18") (pintype "bidirectional"))
    )
    (net (code "139") (name "unconnected-(U3-PB5_(PCINT5)-Pad21)") (class "Default")
      (node (ref "U3") (pin "21") (pinfunction "PB5_(PCINT5)_21") (pintype "bidirectional"))
    )
    (net (code "140") (name "unconnected-(U3-PB6_(PCINT6)-Pad19)") (class "Default")
      (node (ref "U3") (pin "19") (pinfunction "PB6_(PCINT6)_19") (pintype "bidirectional"))
    )
    (net (code "141") (name "unconnected-(U3-PB7_(PCINT7{slash}OC.0A{slash}OC.1C)-Pad20)") (class "Default")
      (node (ref "U3") (pin "20") (pinfunction "PB7_(PCINT7/OC.0A/OC.1C)_20") (pintype "bidirectional"))
    )
    (net (code "142") (name "unconnected-(U3-PC2_(PCINT11{slash}AIN2)-Pad5)") (class "Default")
      (node (ref "U3") (pin "5") (pinfunction "PC2_(PCINT11/AIN2)_5") (pintype "bidirectional"))
    )
    (net (code "143") (name "unconnected-(U3-PC5_(PCINT9{slash}OC.1B)-Pad25)") (class "Default")
      (node (ref "U3") (pin "25") (pinfunction "PC5_(PCINT9/OC.1B)_25") (pintype "bidirectional"))
    )
    (net (code "144") (name "unconnected-(U3-PD0_(OC.0B{slash}INT0)-Pad6)") (class "Default")
      (node (ref "U3") (pin "6") (pinfunction "PD0_(OC.0B/INT0)_6") (pintype "bidirectional"))
    )
    (net (code "145") (name "unconnected-(U3-PD1_(AIN0{slash}INT1)-Pad7)") (class "Default")
      (node (ref "U3") (pin "7") (pinfunction "PD1_(AIN0/INT1)_7") (pintype "bidirectional"))
    )
    (net (code "146") (name "unconnected-(U3-PD6_(~{RTS}{slash}AIN5{slash}INT6)-Pad12)") (class "Default")
      (node (ref "U3") (pin "12") (pinfunction "PD6_(~{RTS}/AIN5/INT6)_12") (pintype "bidirectional"))
    )
    (net (code "147") (name "unconnected-(U5-ADVREF-Pad75)") (class "Default")
      (node (ref "U5") (pin "75") (pinfunction "ADVREF_75") (pintype "passive"))
    )
    (net (code "148") (name "unconnected-(U5-NRST-Pad69)") (class "Default")
      (node (ref "U5") (pin "69") (pinfunction "NRST_69") (pintype "passive"))
    )
    (net (code "149") (name "unconnected-(U5-PB22-Pad141)") (class "Default")
      (node (ref "U5") (pin "141") (pinfunction "PB22_141") (pintype "passive"))
    )
    (net (code "150") (name "unconnected-(U5-PB24-Pad143)") (class "Default")
      (node (ref "U5") (pin "143") (pinfunction "PB24_143") (pintype "passive"))
    )
    (net (code "151") (name "unconnected-(U5-PC10-Pad117)") (class "Default")
      (node (ref "U5") (pin "117") (pinfunction "PC10_117") (pintype "passive"))
    )
    (net (code "152") (name "unconnected-(U5-PC11-Pad93)") (class "Default")
      (node (ref "U5") (pin "93") (pinfunction "PC11_93") (pintype "passive"))
    )
    (net (code "153") (name "unconnected-(U5-PC20-Pad131)") (class "Default")
      (node (ref "U5") (pin "131") (pinfunction "PC20_131") (pintype "passive"))
    )
    (net (code "154") (name "unconnected-(U5-PC27-Pad138)") (class "Default")
      (node (ref "U5") (pin "138") (pinfunction "PC27_138") (pintype "passive"))
    )
    (net (code "155") (name "unconnected-(U5-SHDN-Pad50)") (class "Default")
      (node (ref "U5") (pin "50") (pinfunction "SHDN_50") (pintype "passive"))
    )
    (net (code "156") (name "unconnected-(U5-TST-Pad51)") (class "Default")
      (node (ref "U5") (pin "51") (pinfunction "TST_51") (pintype "passive"))
    )
    (net (code "157") (name "unconnected-(U5-XIN32-Pad48)") (class "Default")
      (node (ref "U5") (pin "48") (pinfunction "XIN32_48") (pintype "passive"))
    )
    (net (code "158") (name "unconnected-(U5-XOUT32-Pad49)") (class "Default")
      (node (ref "U5") (pin "49") (pinfunction "XOUT32_49") (pintype "passive"))
    )
    (net (code "159") (name "unconnected-(USB2-ID-Pad2)") (class "Default")
      (node (ref "USB2") (pin "2") (pinfunction "ID_2") (pintype "passive"))
    )
  )
)
